# Rocekt_test_stand_input.net
KiCad netlist of a schematic drawn in EAGLE
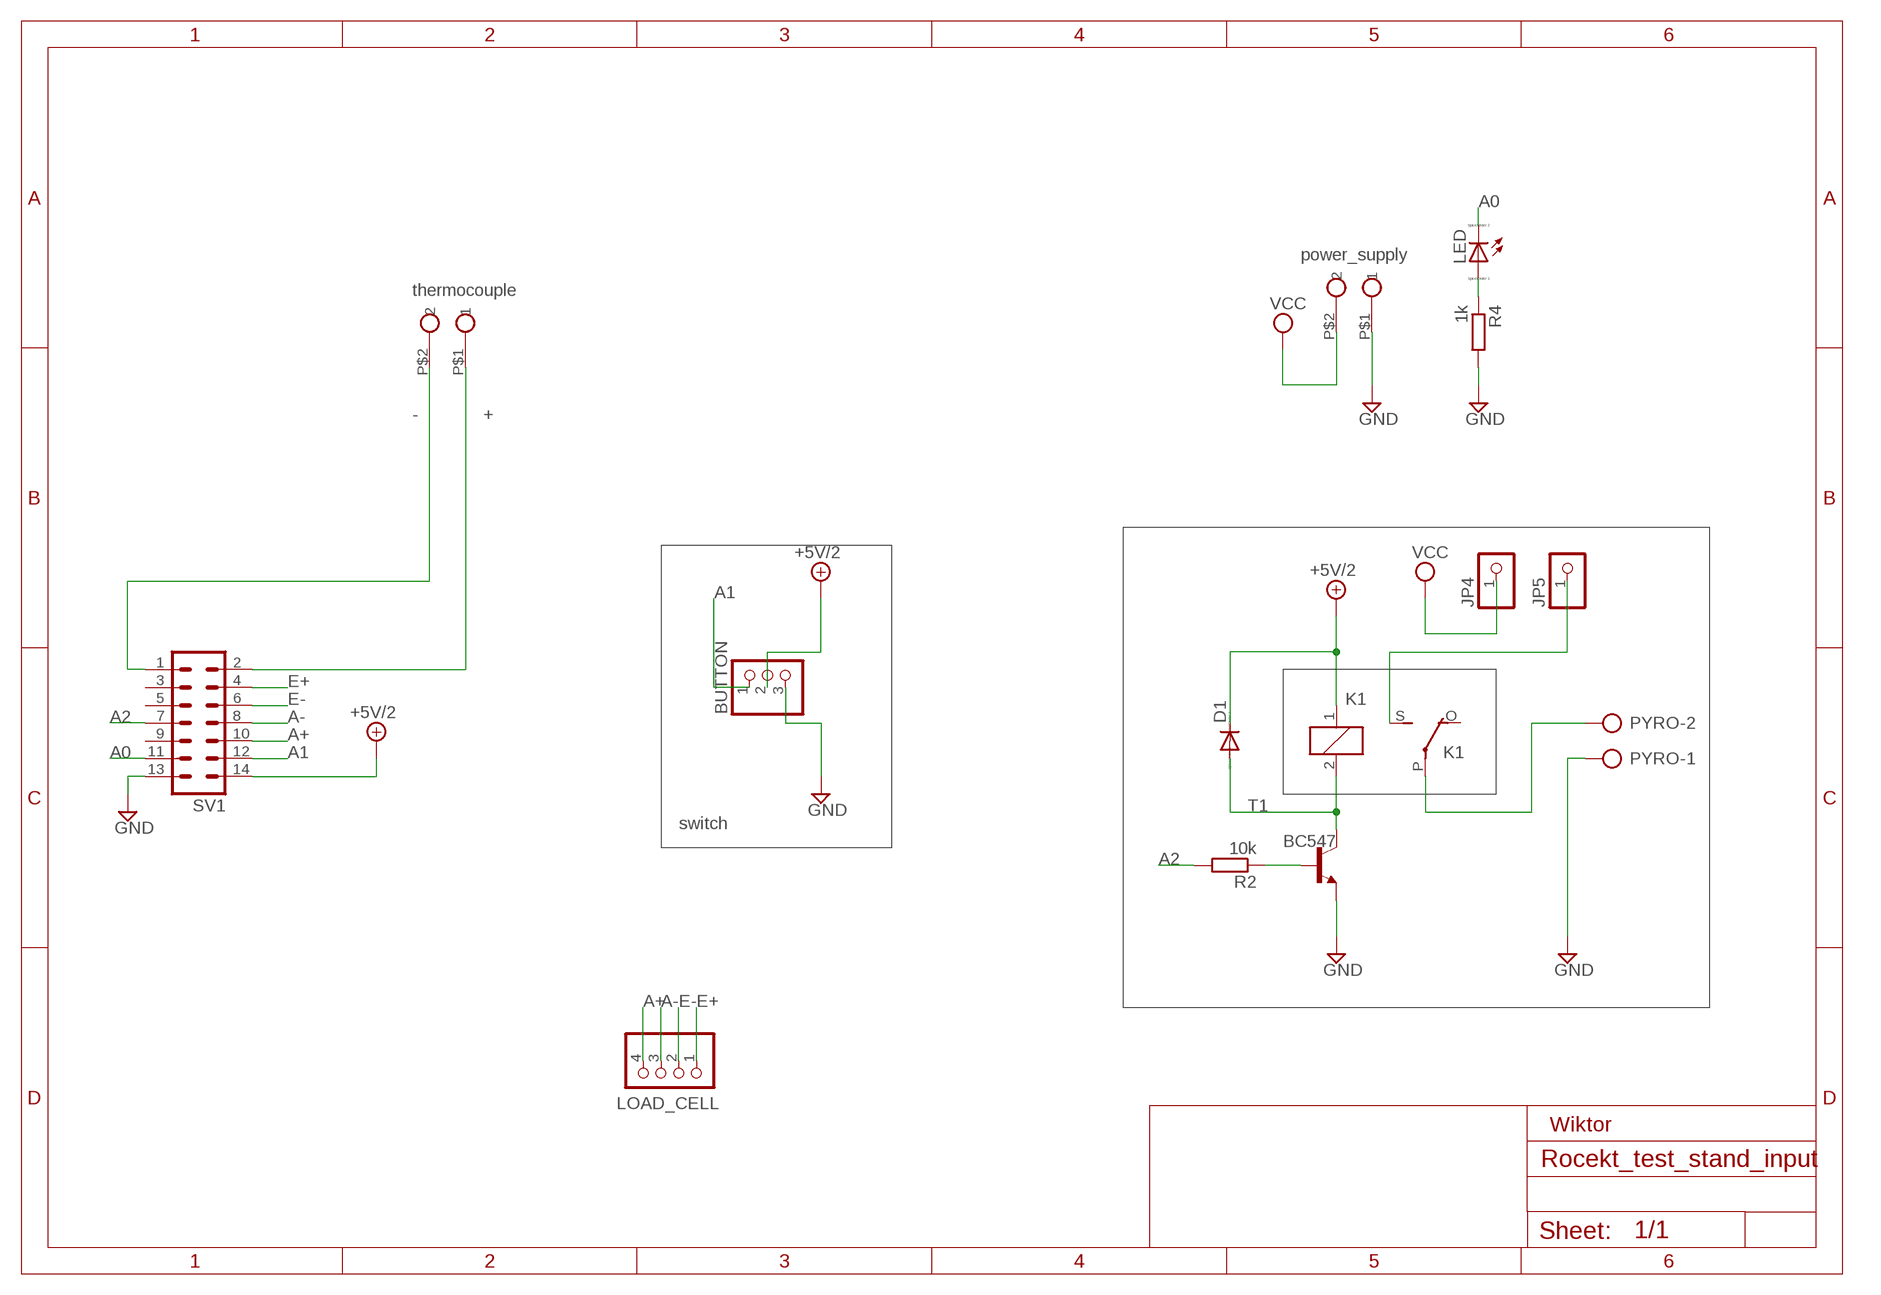
[diagram p0: schematic, sheet 1]

(export (version "E")
  (design (tool "Eeschema 10.0.6"))
  (components
    (comp (ref "BUTTON")
      (value "PINHD-1X3/90")
      (footprint "eagle-import:1X03_90")
      (libsource (lib "eagle-import") (part "PINHD-1X3/90"))
    )
    (comp (ref "D1")
      (value "1N4004")
      (footprint "eagle-import:DO41-10")
      (libsource (lib "eagle-import") (part "1N4004"))
    )
    (comp (ref "JP4")
      (value "PINHD-1X1")
      (footprint "eagle-import:1X01")
      (libsource (lib "eagle-import") (part "PINHD-1X1"))
    )
    (comp (ref "JP5")
      (value "PINHD-1X1")
      (footprint "eagle-import:1X01")
      (libsource (lib "eagle-import") (part "PINHD-1X1"))
    )
    (comp (ref "K1")
      (value "G5L")
      (footprint "eagle-import:G5LE")
      (libsource (lib "eagle-import") (part "G5L"))
    )
    (comp (ref "LED")
      (value "LED_ELD260")
      (footprint "eagle-import:LED_LD260")
      (libsource (lib "eagle-import") (part "LED_ELD260"))
    )
    (comp (ref "LOAD_CELL")
      (value "PINHD-1X4")
      (footprint "eagle-import:1X04")
      (libsource (lib "eagle-import") (part "PINHD-1X4"))
    )
    (comp (ref "POWER_SUPPLY")
      (value "ARK_8.5MM")
      (footprint "eagle-import:ZLACZESRUBOWE8.5MM")
      (libsource (lib "eagle-import") (part "ARK_8.5MM"))
    )
    (comp (ref "PYRO")
      (value "AK500/2")
      (footprint "eagle-import:AK500_2")
      (libsource (lib "eagle-import") (part "AK500/2"))
    )
    (comp (ref "R2")
      (value "10k")
      (footprint "eagle-import:0204_5")
      (libsource (lib "eagle-import") (part "R-EU_0204/5"))
    )
    (comp (ref "R4")
      (value "1k")
      (footprint "eagle-import:0204_5")
      (libsource (lib "eagle-import") (part "R-EU_0204/5"))
    )
    (comp (ref "SV1")
      (value "ML14")
      (footprint "eagle-import:ML14")
      (libsource (lib "eagle-import") (part "ML14"))
    )
    (comp (ref "T1")
      (value "BC547")
      (footprint "eagle-import:TO92")
      (libsource (lib "eagle-import") (part "BC547"))
    )
    (comp (ref "U$1")
      (value "ARK_8.5MM")
      (footprint "eagle-import:ZLACZESRUBOWE8.5MM")
      (libsource (lib "eagle-import") (part "ARK_8.5MM"))
    )
  )
  (nets
    (net (code "1") (name "+5V{slash}2") (class "Default")
      (node (ref "BUTTON") (pin "2") (pinfunction "2_2") (pintype "passive"))
      (node (ref "D1") (pin "C") (pinfunction "C_C") (pintype "passive"))
      (node (ref "K1") (pin "1") (pinfunction "1_1") (pintype "passive"))
      (node (ref "SV1") (pin "14") (pinfunction "14_14") (pintype "passive"))
    )
    (net (code "2") (name "/+") (class "Default")
      (node (ref "SV1") (pin "2") (pinfunction "2_2") (pintype "passive"))
      (node (ref "U$1") (pin "P$1") (pinfunction "1_P$1") (pintype "bidirectional"))
    )
    (net (code "3") (name "/-") (class "Default")
      (node (ref "SV1") (pin "1") (pinfunction "1_1") (pintype "passive"))
      (node (ref "U$1") (pin "P$2") (pinfunction "2_P$2") (pintype "bidirectional"))
    )
    (net (code "4") (name "/A+") (class "Default")
      (node (ref "LOAD_CELL") (pin "4") (pinfunction "4_4") (pintype "passive"))
      (node (ref "SV1") (pin "10") (pinfunction "10_10") (pintype "passive"))
    )
    (net (code "5") (name "/A-") (class "Default")
      (node (ref "LOAD_CELL") (pin "3") (pinfunction "3_3") (pintype "passive"))
      (node (ref "SV1") (pin "8") (pinfunction "8_8") (pintype "passive"))
    )
    (net (code "6") (name "/A0") (class "Default")
      (node (ref "LED") (pin "K") (pinfunction "C_K") (pintype "passive"))
      (node (ref "SV1") (pin "11") (pinfunction "11_11") (pintype "passive"))
    )
    (net (code "7") (name "/A1") (class "Default")
      (node (ref "BUTTON") (pin "1") (pinfunction "1_1") (pintype "passive"))
      (node (ref "SV1") (pin "12") (pinfunction "12_12") (pintype "passive"))
    )
    (net (code "8") (name "/A2") (class "Default")
      (node (ref "R2") (pin "2") (pinfunction "2_2") (pintype "passive"))
      (node (ref "SV1") (pin "7") (pinfunction "7_7") (pintype "passive"))
    )
    (net (code "9") (name "/E+") (class "Default")
      (node (ref "LOAD_CELL") (pin "1") (pinfunction "1_1") (pintype "passive"))
      (node (ref "SV1") (pin "4") (pinfunction "4_4") (pintype "passive"))
    )
    (net (code "10") (name "/E-") (class "Default")
      (node (ref "LOAD_CELL") (pin "2") (pinfunction "2_2") (pintype "passive"))
      (node (ref "SV1") (pin "6") (pinfunction "6_6") (pintype "passive"))
    )
    (net (code "11") (name "GND") (class "Default")
      (node (ref "BUTTON") (pin "3") (pinfunction "3_3") (pintype "passive"))
      (node (ref "POWER_SUPPLY") (pin "P$1") (pinfunction "1_P$1") (pintype "bidirectional"))
      (node (ref "PYRO") (pin "1") (pinfunction "KL_1") (pintype "passive"))
      (node (ref "R4") (pin "2") (pinfunction "2_2") (pintype "passive"))
      (node (ref "SV1") (pin "13") (pinfunction "13_13") (pintype "passive"))
      (node (ref "T1") (pin "1") (pinfunction "E_1") (pintype "passive"))
    )
    (net (code "12") (name "Net-(JP5-Pad1)") (class "Default")
      (node (ref "JP5") (pin "1") (pinfunction "1_1") (pintype "passive"))
      (node (ref "K1") (pin "S") (pinfunction "S_S") (pintype "passive"))
    )
    (net (code "13") (name "Net-(LED-PadA)") (class "Default")
      (node (ref "LED") (pin "A") (pinfunction "A_A") (pintype "passive"))
      (node (ref "R4") (pin "1") (pinfunction "1_1") (pintype "passive"))
    )
    (net (code "14") (name "Net-(PYROB-KL)") (class "Default")
      (node (ref "K1") (pin "P") (pinfunction "P_P") (pintype "passive"))
      (node (ref "PYRO") (pin "2") (pinfunction "KL_2") (pintype "passive"))
    )
    (net (code "15") (name "Net-(T1-B)") (class "Default")
      (node (ref "R2") (pin "1") (pinfunction "1_1") (pintype "passive"))
      (node (ref "T1") (pin "2") (pinfunction "B_2") (pintype "passive"))
    )
    (net (code "16") (name "Net-(T1-C)") (class "Default")
      (node (ref "D1") (pin "A") (pinfunction "A_A") (pintype "passive"))
      (node (ref "K1") (pin "2") (pinfunction "2_2") (pintype "passive"))
      (node (ref "T1") (pin "3") (pinfunction "C_3") (pintype "passive"))
    )
    (net (code "17") (name "VCC") (class "Default")
      (node (ref "JP4") (pin "1") (pinfunction "1_1") (pintype "passive"))
      (node (ref "POWER_SUPPLY") (pin "P$2") (pinfunction "2_P$2") (pintype "bidirectional"))
    )
    (net (code "18") (name "unconnected-(K1-PadO)") (class "Default")
      (node (ref "K1") (pin "O") (pinfunction "O_O") (pintype "passive"))
    )
    (net (code "19") (name "unconnected-(SV1-Pad3)") (class "Default")
      (node (ref "SV1") (pin "3") (pinfunction "3_3") (pintype "passive"))
    )
    (net (code "20") (name "unconnected-(SV1-Pad5)") (class "Default")
      (node (ref "SV1") (pin "5") (pinfunction "5_5") (pintype "passive"))
    )
    (net (code "21") (name "unconnected-(SV1-Pad9)") (class "Default")
      (node (ref "SV1") (pin "9") (pinfunction "9_9") (pintype "passive"))
    )
  )
)
